# VIDEO_DAC_THS8134B.net
KiCad netlist of a schematic drawn in Altium Designer
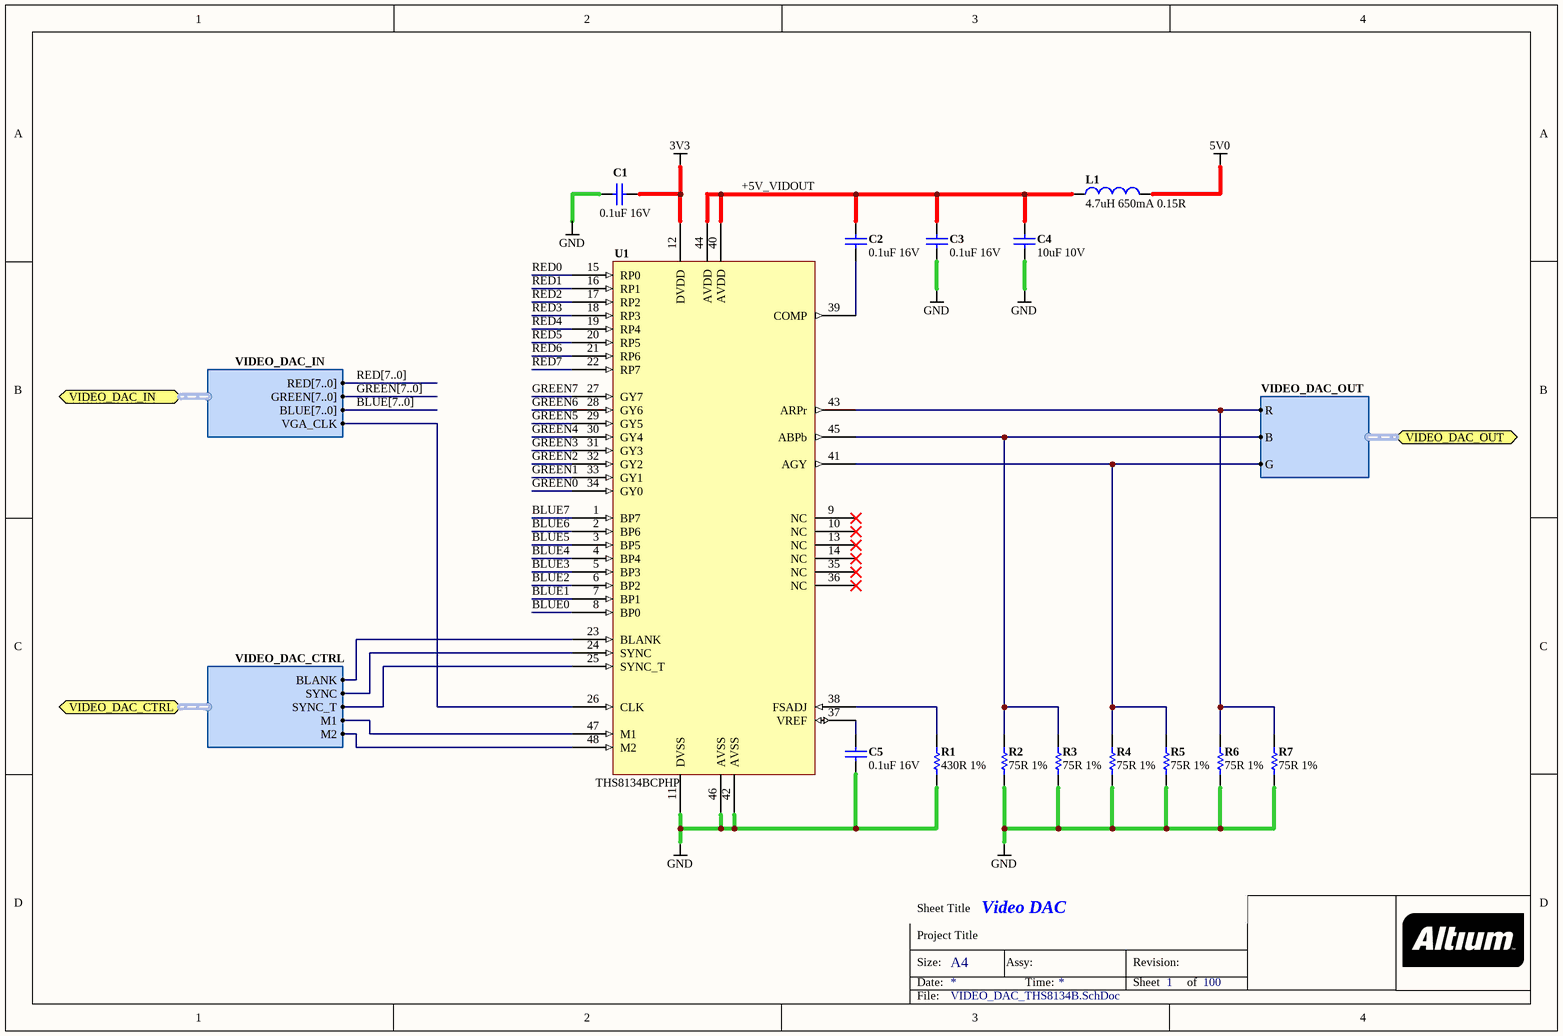
[diagram p0: VIDEO_DAC_THS8134B.SchDoc]

(export (version "E")
  (design (tool "Eeschema 10.0.6"))
  (components
    (comp (ref "C1")
      (value "0.1uF 16V")
      (footprint "CAPC1005-STAR")
      (description "Capacitor, Ceramic, 0.1uF 10% 16V 0402 (1005) X7R")
      (fields (field (name "TOLERANCE") "10 %"))
      (libsource (lib "") (part "CAP-NP_1"))
    )
    (comp (ref "C2")
      (value "0.1uF 16V")
      (footprint "CAPC1005-STAR")
      (description "Capacitor, Ceramic, 0.1uF 10% 16V 0402 (1005) X7R")
      (fields (field (name "TOLERANCE") "10 %"))
      (libsource (lib "AltiumDesignLibrary") (part "CAP-NP"))
    )
    (comp (ref "C3")
      (value "0.1uF 16V")
      (footprint "CAPC1005-STAR")
      (description "Capacitor, Ceramic, 0.1uF 10% 16V 0402 (1005) X7R")
      (fields (field (name "TOLERANCE") "10 %"))
      (libsource (lib "AltiumDesignLibrary") (part "CAP-NP"))
    )
    (comp (ref "C4")
      (value "10uF 10V")
      (footprint "CAPC2012-STAR")
      (description "Capacitor, Ceramic, 10uF 10% 10V 0805 (2012) X5R")
      (fields (field (name "TOLERANCE") "10 %"))
      (libsource (lib "AltiumDesignLibrary") (part "CAP-NP"))
    )
    (comp (ref "C5")
      (value "0.1uF 16V")
      (footprint "CAPC1005-STAR")
      (description "Capacitor, Ceramic, 0.1uF 10% 16V 0402 (1005) X7R")
      (fields (field (name "TOLERANCE") "10 %"))
      (libsource (lib "AltiumDesignLibrary") (part "CAP-NP"))
    )
    (comp (ref "L1")
      (value "4.7uH 650mA 0.15R")
      (footprint "INDC3225")
      (description "Inductor, 4.7uH 650mA 0.15R 1210 (3225) LQH32CN4R7M11L")
      (libsource (lib "AltiumDesignLibrary") (part "IND"))
    )
    (comp (ref "R1")
      (value "430R 1%")
      (footprint "RESC1005-STAR")
      (description "Resistor, 430R 1% 0402 (1005)")
      (fields (field (name "TOLERANCE") "1 %"))
      (libsource (lib "AltiumDesignLibrary") (part "RES"))
    )
    (comp (ref "R2")
      (value "75R 1%")
      (footprint "RESC1005-STAR")
      (description "Resistor, 75R 1% 0402")
      (fields (field (name "TOLERANCE") "1 %"))
      (libsource (lib "AltiumDesignLibrary") (part "RES"))
    )
    (comp (ref "R3")
      (value "75R 1%")
      (footprint "RESC1005-STAR")
      (description "Resistor, 75R 1% 0402")
      (fields (field (name "TOLERANCE") "1 %"))
      (libsource (lib "AltiumDesignLibrary") (part "RES"))
    )
    (comp (ref "R4")
      (value "75R 1%")
      (footprint "RESC1005-STAR")
      (description "Resistor, 75R 1% 0402")
      (fields (field (name "TOLERANCE") "1 %"))
      (libsource (lib "AltiumDesignLibrary") (part "RES"))
    )
    (comp (ref "R5")
      (value "75R 1%")
      (footprint "RESC1005-STAR")
      (description "Resistor, 75R 1% 0402")
      (fields (field (name "TOLERANCE") "1 %"))
      (libsource (lib "AltiumDesignLibrary") (part "RES"))
    )
    (comp (ref "R6")
      (value "75R 1%")
      (footprint "RESC1005-STAR")
      (description "Resistor, 75R 1% 0402")
      (fields (field (name "TOLERANCE") "1 %"))
      (libsource (lib "AltiumDesignLibrary") (part "RES"))
    )
    (comp (ref "R7")
      (value "75R 1%")
      (footprint "RESC1005-STAR")
      (description "Resistor, 75R 1% 0402")
      (fields (field (name "TOLERANCE") "1 %"))
      (libsource (lib "AltiumDesignLibrary") (part "RES"))
    )
    (comp (ref "U1")
      (value "THS8134BCPHP")
      (footprint "TSQFP50P900X900_HS-48")
      (description "THS8134BCPHP, Triple 8-Bit, 80 MSPS Video DAC with Tri-Level Sync Generation")
      (libsource (lib "AltiumDesignLibrary") (part "THS8134"))
    )
  )
  (nets
    (net (code "4") (name "/+5V_VIDOUT") (class "Default")
      (node (ref "C2") (pin "1") (pinfunction "1_1") (pintype "passive"))
      (node (ref "C3") (pin "1") (pinfunction "1_1") (pintype "passive"))
      (node (ref "C4") (pin "2") (pinfunction "2_2") (pintype "passive"))
      (node (ref "L1") (pin "2") (pinfunction "2_2") (pintype "passive"))
      (node (ref "U1") (pin "40") (pinfunction "AVDD_40") (pintype "power_in"))
      (node (ref "U1") (pin "44") (pinfunction "AVDD_44") (pintype "power_in"))
    )
    (net (code "5") (name "/B") (class "Default")
      (node (ref "R2") (pin "1") (pinfunction "1_1") (pintype "passive"))
      (node (ref "R3") (pin "2") (pinfunction "2_2") (pintype "passive"))
      (node (ref "U1") (pin "45") (pinfunction "ABPb_45") (pintype "output"))
    )
    (net (code "6") (name "/BLANK") (class "Default")
      (node (ref "U1") (pin "23") (pinfunction "BLANK_23") (pintype "input"))
    )
    (net (code "7") (name "/BLUE0") (class "Default")
      (node (ref "U1") (pin "8") (pinfunction "BP0_8") (pintype "input"))
    )
    (net (code "8") (name "/BLUE1") (class "Default")
      (node (ref "U1") (pin "7") (pinfunction "BP1_7") (pintype "input"))
    )
    (net (code "9") (name "/BLUE2") (class "Default")
      (node (ref "U1") (pin "6") (pinfunction "BP2_6") (pintype "input"))
    )
    (net (code "10") (name "/BLUE3") (class "Default")
      (node (ref "U1") (pin "5") (pinfunction "BP3_5") (pintype "input"))
    )
    (net (code "11") (name "/BLUE4") (class "Default")
      (node (ref "U1") (pin "4") (pinfunction "BP4_4") (pintype "input"))
    )
    (net (code "12") (name "/BLUE5") (class "Default")
      (node (ref "U1") (pin "3") (pinfunction "BP5_3") (pintype "input"))
    )
    (net (code "13") (name "/BLUE6") (class "Default")
      (node (ref "U1") (pin "2") (pinfunction "BP6_2") (pintype "input"))
    )
    (net (code "14") (name "/BLUE7") (class "Default")
      (node (ref "U1") (pin "1") (pinfunction "BP7_1") (pintype "input"))
    )
    (net (code "15") (name "/G") (class "Default")
      (node (ref "R4") (pin "1") (pinfunction "1_1") (pintype "passive"))
      (node (ref "R5") (pin "2") (pinfunction "2_2") (pintype "passive"))
      (node (ref "U1") (pin "41") (pinfunction "AGY_41") (pintype "output"))
    )
    (net (code "16") (name "/GREEN0") (class "Default")
      (node (ref "U1") (pin "34") (pinfunction "GY0_34") (pintype "input"))
    )
    (net (code "17") (name "/GREEN1") (class "Default")
      (node (ref "U1") (pin "33") (pinfunction "GY1_33") (pintype "input"))
    )
    (net (code "18") (name "/GREEN2") (class "Default")
      (node (ref "U1") (pin "32") (pinfunction "GY2_32") (pintype "input"))
    )
    (net (code "19") (name "/GREEN3") (class "Default")
      (node (ref "U1") (pin "31") (pinfunction "GY3_31") (pintype "input"))
    )
    (net (code "20") (name "/GREEN4") (class "Default")
      (node (ref "U1") (pin "30") (pinfunction "GY4_30") (pintype "input"))
    )
    (net (code "21") (name "/GREEN5") (class "Default")
      (node (ref "U1") (pin "29") (pinfunction "GY5_29") (pintype "input"))
    )
    (net (code "22") (name "/GREEN6") (class "Default")
      (node (ref "U1") (pin "28") (pinfunction "GY6_28") (pintype "input"))
    )
    (net (code "23") (name "/GREEN7") (class "Default")
      (node (ref "U1") (pin "27") (pinfunction "GY7_27") (pintype "input"))
    )
    (net (code "25") (name "/M1") (class "Default")
      (node (ref "U1") (pin "47") (pinfunction "M1_47") (pintype "input"))
    )
    (net (code "26") (name "/M2") (class "Default")
      (node (ref "U1") (pin "48") (pinfunction "M2_48") (pintype "input"))
    )
    (net (code "27") (name "/R") (class "Default")
      (node (ref "R6") (pin "2") (pinfunction "2_2") (pintype "passive"))
      (node (ref "R7") (pin "2") (pinfunction "2_2") (pintype "passive"))
      (node (ref "U1") (pin "43") (pinfunction "ARPr_43") (pintype "output"))
    )
    (net (code "28") (name "/RED0") (class "Default")
      (node (ref "U1") (pin "15") (pinfunction "RP0_15") (pintype "input"))
    )
    (net (code "29") (name "/RED1") (class "Default")
      (node (ref "U1") (pin "16") (pinfunction "RP1_16") (pintype "input"))
    )
    (net (code "30") (name "/RED2") (class "Default")
      (node (ref "U1") (pin "17") (pinfunction "RP2_17") (pintype "input"))
    )
    (net (code "31") (name "/RED3") (class "Default")
      (node (ref "U1") (pin "18") (pinfunction "RP3_18") (pintype "input"))
    )
    (net (code "32") (name "/RED4") (class "Default")
      (node (ref "U1") (pin "19") (pinfunction "RP4_19") (pintype "input"))
    )
    (net (code "33") (name "/RED5") (class "Default")
      (node (ref "U1") (pin "20") (pinfunction "RP5_20") (pintype "input"))
    )
    (net (code "34") (name "/RED6") (class "Default")
      (node (ref "U1") (pin "21") (pinfunction "RP6_21") (pintype "input"))
    )
    (net (code "35") (name "/RED7") (class "Default")
      (node (ref "U1") (pin "22") (pinfunction "RP7_22") (pintype "input"))
    )
    (net (code "37") (name "/SYNC") (class "Default")
      (node (ref "U1") (pin "24") (pinfunction "SYNC_24") (pintype "input"))
    )
    (net (code "38") (name "/SYNC_T") (class "Default")
      (node (ref "U1") (pin "25") (pinfunction "SYNC_T_25") (pintype "input"))
    )
    (net (code "39") (name "/VGA_CLK") (class "Default")
      (node (ref "U1") (pin "26") (pinfunction "CLK_26") (pintype "input"))
    )
    (net (code "44") (name "3V3") (class "Default")
      (node (ref "C1") (pin "1") (pinfunction "1_1") (pintype "passive"))
      (node (ref "U1") (pin "12") (pinfunction "DVDD_12") (pintype "power_in"))
    )
    (net (code "45") (name "5V0") (class "Default")
      (node (ref "L1") (pin "1") (pinfunction "1_1") (pintype "passive"))
    )
    (net (code "46") (name "GND") (class "Default")
      (node (ref "C1") (pin "2") (pinfunction "2_2") (pintype "passive"))
      (node (ref "C3") (pin "2") (pinfunction "2_2") (pintype "passive"))
      (node (ref "C4") (pin "1") (pinfunction "1_1") (pintype "passive"))
      (node (ref "C5") (pin "2") (pinfunction "2_2") (pintype "passive"))
      (node (ref "R1") (pin "1") (pinfunction "1_1") (pintype "passive"))
      (node (ref "R2") (pin "2") (pinfunction "2_2") (pintype "passive"))
      (node (ref "R3") (pin "1") (pinfunction "1_1") (pintype "passive"))
      (node (ref "R4") (pin "2") (pinfunction "2_2") (pintype "passive"))
      (node (ref "R5") (pin "1") (pinfunction "1_1") (pintype "passive"))
      (node (ref "R6") (pin "1") (pinfunction "1_1") (pintype "passive"))
      (node (ref "R7") (pin "1") (pinfunction "1_1") (pintype "passive"))
      (node (ref "U1") (pin "11") (pinfunction "DVSS_11") (pintype "power_in"))
      (node (ref "U1") (pin "42") (pinfunction "AVSS_42") (pintype "power_in"))
      (node (ref "U1") (pin "46") (pinfunction "AVSS_46") (pintype "power_in"))
    )
    (net (code "47") (name "Net-(U1-COMP)") (class "Default")
      (node (ref "C2") (pin "2") (pinfunction "2_2") (pintype "passive"))
      (node (ref "U1") (pin "39") (pinfunction "COMP_39") (pintype "output"))
    )
    (net (code "48") (name "Net-(U1-FSADJ)") (class "Default")
      (node (ref "R1") (pin "2") (pinfunction "2_2") (pintype "passive"))
      (node (ref "U1") (pin "38") (pinfunction "FSADJ_38") (pintype "input"))
    )
    (net (code "49") (name "Net-(U1-VREF)") (class "Default")
      (node (ref "C5") (pin "1") (pinfunction "1_1") (pintype "passive"))
      (node (ref "U1") (pin "37") (pinfunction "VREF_37") (pintype "bidirectional"))
    )
    (net (code "50") (name "unconnected-(U1-NC-Pad9)") (class "Default")
      (node (ref "U1") (pin "9") (pinfunction "NC_9") (pintype "passive+no_connect"))
    )
    (net (code "51") (name "unconnected-(U1-NC-Pad10)") (class "Default")
      (node (ref "U1") (pin "10") (pinfunction "NC_10") (pintype "passive+no_connect"))
    )
    (net (code "52") (name "unconnected-(U1-NC-Pad13)") (class "Default")
      (node (ref "U1") (pin "13") (pinfunction "NC_13") (pintype "passive+no_connect"))
    )
    (net (code "53") (name "unconnected-(U1-NC-Pad14)") (class "Default")
      (node (ref "U1") (pin "14") (pinfunction "NC_14") (pintype "passive+no_connect"))
    )
    (net (code "54") (name "unconnected-(U1-NC-Pad35)") (class "Default")
      (node (ref "U1") (pin "35") (pinfunction "NC_35") (pintype "passive+no_connect"))
    )
    (net (code "55") (name "unconnected-(U1-NC-Pad36)") (class "Default")
      (node (ref "U1") (pin "36") (pinfunction "NC_36") (pintype "passive+no_connect"))
    )
  )
)
